# IMU.net
KiCad netlist of a schematic drawn in Altium Designer
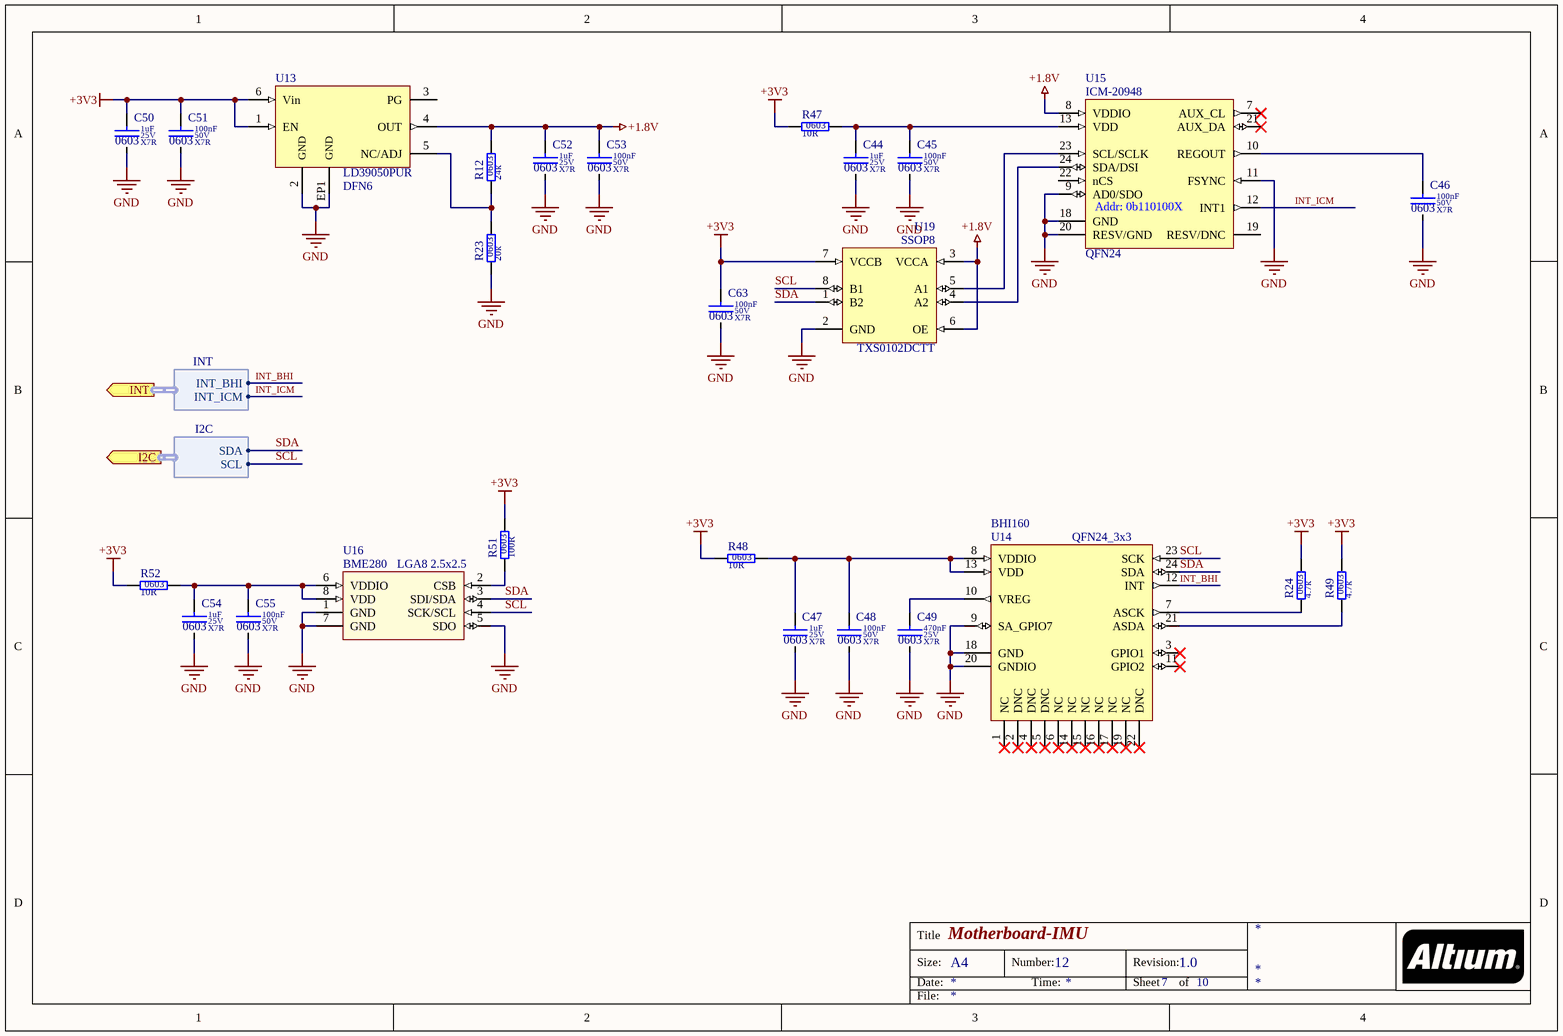
[diagram p0: IMU.SchDoc]

(export (version "E")
  (design (tool "Eeschema 10.0.6"))
  (components
    (comp (ref "C44")
      (value "1uF")
      (footprint "C_0603_1608")
      (description "Capacitor")
      (fields
        (field (name "DIELECTRIC") "X7R")
        (field (name "VOLTAGE") "25V")
        (field (name "SCH_FOOTPRINT") "0603")
        (field (name "PART NUMBER") "C_1uF_25V_X7R_0603_10")
        (field (name "MANUFACTURER") "Samsung")
      )
      (libsource (lib "Library") (part "C"))
    )
    (comp (ref "C45")
      (value "100nF")
      (footprint "C_0603_1608")
      (description "Capacitor")
      (fields
        (field (name "DIELECTRIC") "X7R")
        (field (name "VOLTAGE") "50V")
        (field (name "SCH_FOOTPRINT") "0603")
        (field (name "PART NUMBER") "C_100nF_50V_X7R_0603_5")
        (field (name "MANUFACTURER") "Samsung")
      )
      (libsource (lib "Library") (part "C"))
    )
    (comp (ref "C46")
      (value "100nF")
      (footprint "C_0603_1608")
      (description "Capacitor")
      (fields
        (field (name "DIELECTRIC") "X7R")
        (field (name "VOLTAGE") "50V")
        (field (name "SCH_FOOTPRINT") "0603")
        (field (name "PART NUMBER") "C_100nF_50V_X7R_0603_5")
        (field (name "MANUFACTURER") "Samsung")
      )
      (libsource (lib "Library") (part "C"))
    )
    (comp (ref "C47")
      (value "1uF")
      (footprint "C_0603_1608")
      (description "Capacitor")
      (fields
        (field (name "DIELECTRIC") "X7R")
        (field (name "VOLTAGE") "25V")
        (field (name "SCH_FOOTPRINT") "0603")
        (field (name "PART NUMBER") "C_1uF_25V_X7R_0603_10")
        (field (name "MANUFACTURER") "Samsung")
      )
      (libsource (lib "Library") (part "C"))
    )
    (comp (ref "C48")
      (value "100nF")
      (footprint "C_0603_1608")
      (description "Capacitor")
      (fields
        (field (name "DIELECTRIC") "X7R")
        (field (name "VOLTAGE") "50V")
        (field (name "SCH_FOOTPRINT") "0603")
        (field (name "PART NUMBER") "C_100nF_50V_X7R_0603_5")
        (field (name "MANUFACTURER") "Samsung")
      )
      (libsource (lib "Library") (part "C"))
    )
    (comp (ref "C49")
      (value "470nF")
      (footprint "C_0603_1608")
      (description "Capacitor")
      (fields
        (field (name "DIELECTRIC") "X7R")
        (field (name "VOLTAGE") "25V")
        (field (name "SCH_FOOTPRINT") "0603")
        (field (name "PART NUMBER") "C_470nF_25V_X7R_0603_10")
        (field (name "MANUFACTURER") "Murata")
      )
      (libsource (lib "Library") (part "C"))
    )
    (comp (ref "C50")
      (value "1uF")
      (footprint "C_0603_1608")
      (description "Capacitor")
      (fields
        (field (name "DIELECTRIC") "X7R")
        (field (name "VOLTAGE") "25V")
        (field (name "SCH_FOOTPRINT") "0603")
        (field (name "PART NUMBER") "C_1uF_25V_X7R_0603_10")
        (field (name "MANUFACTURER") "Samsung")
      )
      (libsource (lib "Library") (part "C"))
    )
    (comp (ref "C51")
      (value "100nF")
      (footprint "C_0603_1608")
      (description "Capacitor")
      (fields
        (field (name "DIELECTRIC") "X7R")
        (field (name "VOLTAGE") "50V")
        (field (name "SCH_FOOTPRINT") "0603")
        (field (name "PART NUMBER") "C_100nF_50V_X7R_0603_5")
        (field (name "MANUFACTURER") "Samsung")
      )
      (libsource (lib "Library") (part "C"))
    )
    (comp (ref "C52")
      (value "1uF")
      (footprint "C_0603_1608")
      (description "Capacitor")
      (fields
        (field (name "DIELECTRIC") "X7R")
        (field (name "VOLTAGE") "25V")
        (field (name "SCH_FOOTPRINT") "0603")
        (field (name "PART NUMBER") "C_1uF_25V_X7R_0603_10")
        (field (name "MANUFACTURER") "Samsung")
      )
      (libsource (lib "Library") (part "C"))
    )
    (comp (ref "C53")
      (value "100nF")
      (footprint "C_0603_1608")
      (description "Capacitor")
      (fields
        (field (name "DIELECTRIC") "X7R")
        (field (name "VOLTAGE") "50V")
        (field (name "SCH_FOOTPRINT") "0603")
        (field (name "PART NUMBER") "C_100nF_50V_X7R_0603_5")
        (field (name "MANUFACTURER") "Samsung")
      )
      (libsource (lib "Library") (part "C"))
    )
    (comp (ref "C54")
      (value "1uF")
      (footprint "C_0603_1608")
      (description "Capacitor")
      (fields
        (field (name "DIELECTRIC") "X7R")
        (field (name "VOLTAGE") "25V")
        (field (name "SCH_FOOTPRINT") "0603")
        (field (name "PART NUMBER") "C_1uF_25V_X7R_0603_10")
        (field (name "MANUFACTURER") "Samsung")
      )
      (libsource (lib "Library") (part "C"))
    )
    (comp (ref "C55")
      (value "100nF")
      (footprint "C_0603_1608")
      (description "Capacitor")
      (fields
        (field (name "DIELECTRIC") "X7R")
        (field (name "VOLTAGE") "50V")
        (field (name "SCH_FOOTPRINT") "0603")
        (field (name "PART NUMBER") "C_100nF_50V_X7R_0603_5")
        (field (name "MANUFACTURER") "Samsung")
      )
      (libsource (lib "Library") (part "C"))
    )
    (comp (ref "C63")
      (value "100nF")
      (footprint "C_0603_1608")
      (description "Capacitor")
      (fields
        (field (name "DIELECTRIC") "X7R")
        (field (name "VOLTAGE") "50V")
        (field (name "SCH_FOOTPRINT") "0603")
        (field (name "PART NUMBER") "C_100nF_50V_X7R_0603_5")
        (field (name "MANUFACTURER") "Samsung")
      )
      (libsource (lib "Library") (part "C"))
    )
    (comp (ref "R12")
      (value "24k")
      (footprint "R_0603_1608")
      (fields
        (field (name "SCH_FOOTPRINT") "0603")
        (field (name "PART NUMBER") "R_24k_0603_1")
        (field (name "VOLTAGE") "75V")
        (field (name "POWER") "100mW")
      )
      (libsource (lib "Library") (part "R"))
    )
    (comp (ref "R23")
      (value "20k")
      (footprint "R_0603_1608")
      (fields
        (field (name "SCH_FOOTPRINT") "0603")
        (field (name "PART NUMBER") "R_20k_0603_1")
        (field (name "VOLTAGE") "75V")
        (field (name "POWER") "100mW")
      )
      (libsource (lib "Library") (part "R"))
    )
    (comp (ref "R24")
      (value "4.7k")
      (footprint "R_0603_1608")
      (fields
        (field (name "SCH_FOOTPRINT") "0603")
        (field (name "PART NUMBER") "R_4.7k_0603_1")
        (field (name "VOLTAGE") "75V")
        (field (name "POWER") "100mW")
      )
      (libsource (lib "Library") (part "R"))
    )
    (comp (ref "R47")
      (value "10R")
      (footprint "R_0603_1608")
      (fields
        (field (name "SCH_FOOTPRINT") "0603")
        (field (name "PART NUMBER") "R_10R_0603_1")
        (field (name "VOLTAGE") "50V")
        (field (name "POWER") "100mW")
      )
      (libsource (lib "Library") (part "R"))
    )
    (comp (ref "R48")
      (value "10R")
      (footprint "R_0603_1608")
      (fields
        (field (name "SCH_FOOTPRINT") "0603")
        (field (name "PART NUMBER") "R_10R_0603_1")
        (field (name "VOLTAGE") "50V")
        (field (name "POWER") "100mW")
      )
      (libsource (lib "Library") (part "R"))
    )
    (comp (ref "R49")
      (value "4.7k")
      (footprint "R_0603_1608")
      (fields
        (field (name "SCH_FOOTPRINT") "0603")
        (field (name "PART NUMBER") "R_4.7k_0603_1")
        (field (name "VOLTAGE") "75V")
        (field (name "POWER") "100mW")
      )
      (libsource (lib "Library") (part "R"))
    )
    (comp (ref "R51")
      (value "100R")
      (footprint "R_0603_1608")
      (fields
        (field (name "SCH_FOOTPRINT") "0603")
        (field (name "PART NUMBER") "R_100R_0603_1")
        (field (name "VOLTAGE") "50V")
        (field (name "POWER") "100mW")
      )
      (libsource (lib "Library") (part "R"))
    )
    (comp (ref "R52")
      (value "10R")
      (footprint "R_0603_1608")
      (fields
        (field (name "SCH_FOOTPRINT") "0603")
        (field (name "PART NUMBER") "R_10R_0603_1")
        (field (name "VOLTAGE") "50V")
        (field (name "POWER") "100mW")
      )
      (libsource (lib "Library") (part "R"))
    )
    (comp (ref "U13")
      (value "LD39050PUR")
      (footprint "DFN6_3x3")
      (fields
        (field (name "SCH_FOOTPRINT") "DFN6")
        (field (name "PART NUMBER") "VL_LD39050PUR")
        (field (name "VOLTAGE") "ADJ")
        (field (name "MANUFACTURER") "STMicroelectronics")
      )
      (libsource (lib "Library") (part "VL_LD39050"))
    )
    (comp (ref "U14")
      (value "BHI160")
      (footprint "QFN24_3x3")
      (fields
        (field (name "SCH_FOOTPRINT") "QFN24_3x3")
        (field (name "PART NUMBER") "U_BHI160")
        (field (name "MANUFACTURER") "Bosch Tools")
        (field (name "Comment") "Three Axis Ultra Low Power Sensor Hub - LGA-24")
      )
      (libsource (lib "Library") (part "U_BHI160"))
    )
    (comp (ref "U15")
      (value "ICM-20948")
      (footprint "QFN24_3x3")
      (fields
        (field (name "SCH_FOOTPRINT") "QFN24")
        (field (name "PART NUMBER") "U_ICM-20948")
        (field (name "MANUFACTURER") "TDK")
        (field (name "Comment") "9-Axis MEMS MotionTracking Device")
      )
      (libsource (lib "Library") (part "U_ICM-20948"))
    )
    (comp (ref "U16")
      (value "BME280")
      (footprint "LGA8_2.5x2.5")
      (fields
        (field (name "SCH_FOOTPRINT") "LGA8 2.5x2.5")
        (field (name "PART NUMBER") "U_BME280")
        (field (name "MANUFACTURER") "Bosch Tools")
        (field (name "Comment") "Combined humidity and pressure sensor")
      )
      (libsource (lib "Library") (part "U_BME280"))
    )
    (comp (ref "U19")
      (value "TXS0102DCTT")
      (footprint "SSOP8_3x3")
      (fields
        (field (name "SCH_FOOTPRINT") "SSOP8")
        (field (name "PART NUMBER") "U_TXS0102DCTT")
        (field (name "MANUFACTURER") "Texas Instruments")
      )
      (libsource (lib "Library") (part "U_TXS0102_DCT_DCU"))
    )
  )
  (nets
    (net (code "3") (name "+1.8V") (class "Default")
      (node (ref "C52") (pin "1") (pinfunction "1_1") (pintype "passive"))
      (node (ref "C53") (pin "1") (pinfunction "1_1") (pintype "passive"))
      (node (ref "R12") (pin "2") (pinfunction "2_2") (pintype "passive"))
      (node (ref "U13") (pin "4") (pinfunction "OUT_4") (pintype "output"))
      (node (ref "U15") (pin "8") (pinfunction "VDDIO_8") (pintype "input"))
      (node (ref "U19") (pin "3") (pinfunction "VCCA_3") (pintype "input"))
      (node (ref "U19") (pin "6") (pinfunction "OE_6") (pintype "input"))
    )
    (net (code "4") (name "+3V3") (class "Default")
      (node (ref "C50") (pin "1") (pinfunction "1_1") (pintype "passive"))
      (node (ref "C51") (pin "1") (pinfunction "1_1") (pintype "passive"))
      (node (ref "C63") (pin "1") (pinfunction "1_1") (pintype "passive"))
      (node (ref "R24") (pin "2") (pinfunction "2_2") (pintype "passive"))
      (node (ref "R47") (pin "1") (pinfunction "1_1") (pintype "passive"))
      (node (ref "R48") (pin "1") (pinfunction "1_1") (pintype "passive"))
      (node (ref "R49") (pin "2") (pinfunction "2_2") (pintype "passive"))
      (node (ref "R51") (pin "2") (pinfunction "2_2") (pintype "passive"))
      (node (ref "R52") (pin "1") (pinfunction "1_1") (pintype "passive"))
      (node (ref "U13") (pin "1") (pinfunction "EN_1") (pintype "input"))
      (node (ref "U13") (pin "6") (pinfunction "Vin_6") (pintype "input"))
      (node (ref "U19") (pin "7") (pinfunction "VCCB_7") (pintype "input"))
    )
    (net (code "5") (name "/INT_BHI") (class "Default")
      (node (ref "U14") (pin "12") (pinfunction "INT_12") (pintype "output"))
    )
    (net (code "6") (name "/INT_ICM") (class "Default")
      (node (ref "U15") (pin "12") (pinfunction "INT1_12") (pintype "output"))
    )
    (net (code "7") (name "/SCL") (class "Default")
      (node (ref "U14") (pin "23") (pinfunction "SCK_23") (pintype "input"))
      (node (ref "U16") (pin "4") (pinfunction "SCK/SCL_4") (pintype "input"))
      (node (ref "U19") (pin "8") (pinfunction "B1_8") (pintype "bidirectional"))
    )
    (net (code "8") (name "/SDA") (class "Default")
      (node (ref "U14") (pin "24") (pinfunction "SDA_24") (pintype "bidirectional"))
      (node (ref "U16") (pin "3") (pinfunction "SDI/SDA_3") (pintype "bidirectional"))
      (node (ref "U19") (pin "1") (pinfunction "B2_1") (pintype "bidirectional"))
    )
    (net (code "11") (name "GND") (class "Default")
      (node (ref "C44") (pin "2") (pinfunction "2_2") (pintype "passive"))
      (node (ref "C45") (pin "2") (pinfunction "2_2") (pintype "passive"))
      (node (ref "C46") (pin "2") (pinfunction "2_2") (pintype "passive"))
      (node (ref "C47") (pin "2") (pinfunction "2_2") (pintype "passive"))
      (node (ref "C48") (pin "2") (pinfunction "2_2") (pintype "passive"))
      (node (ref "C49") (pin "2") (pinfunction "2_2") (pintype "passive"))
      (node (ref "C50") (pin "2") (pinfunction "2_2") (pintype "passive"))
      (node (ref "C51") (pin "2") (pinfunction "2_2") (pintype "passive"))
      (node (ref "C52") (pin "2") (pinfunction "2_2") (pintype "passive"))
      (node (ref "C53") (pin "2") (pinfunction "2_2") (pintype "passive"))
      (node (ref "C54") (pin "2") (pinfunction "2_2") (pintype "passive"))
      (node (ref "C55") (pin "2") (pinfunction "2_2") (pintype "passive"))
      (node (ref "C63") (pin "2") (pinfunction "2_2") (pintype "passive"))
      (node (ref "R23") (pin "1") (pinfunction "1_1") (pintype "passive"))
      (node (ref "U13") (pin "2") (pinfunction "GND_2") (pintype "power_in"))
      (node (ref "U13") (pin "EP1") (pinfunction "GND_EP1") (pintype "power_in"))
      (node (ref "U14") (pin "18") (pinfunction "GND_18") (pintype "power_in"))
      (node (ref "U14") (pin "20") (pinfunction "GNDIO_20") (pintype "power_in"))
      (node (ref "U14") (pin "9") (pinfunction "SA_GPIO7_9") (pintype "bidirectional"))
      (node (ref "U15") (pin "11") (pinfunction "FSYNC_11") (pintype "input"))
      (node (ref "U15") (pin "18") (pinfunction "GND_18") (pintype "power_in"))
      (node (ref "U15") (pin "20") (pinfunction "RESV/GND_20") (pintype "power_in"))
      (node (ref "U15") (pin "9") (pinfunction "AD0/SDO_9") (pintype "bidirectional"))
      (node (ref "U16") (pin "1") (pinfunction "GND_1") (pintype "power_in"))
      (node (ref "U16") (pin "5") (pinfunction "SDO_5") (pintype "bidirectional"))
      (node (ref "U16") (pin "7") (pinfunction "GND_7") (pintype "power_in"))
      (node (ref "U19") (pin "2") (pinfunction "GND_2") (pintype "power_in"))
    )
    (net (code "12") (name "Net-(U13-NC{slash}ADJ)") (class "Default")
      (node (ref "R12") (pin "1") (pinfunction "1_1") (pintype "passive"))
      (node (ref "R23") (pin "2") (pinfunction "2_2") (pintype "passive"))
      (node (ref "U13") (pin "5") (pinfunction "NC/ADJ_5") (pintype "passive"))
    )
    (net (code "13") (name "Net-(U14-ASCK)") (class "Default")
      (node (ref "R24") (pin "1") (pinfunction "1_1") (pintype "passive"))
      (node (ref "U14") (pin "7") (pinfunction "ASCK_7") (pintype "output"))
    )
    (net (code "14") (name "Net-(U14-ASDA)") (class "Default")
      (node (ref "R49") (pin "1") (pinfunction "1_1") (pintype "passive"))
      (node (ref "U14") (pin "21") (pinfunction "ASDA_21") (pintype "bidirectional"))
    )
    (net (code "15") (name "Net-(U14-VDD)") (class "Default")
      (node (ref "C47") (pin "1") (pinfunction "1_1") (pintype "passive"))
      (node (ref "C48") (pin "1") (pinfunction "1_1") (pintype "passive"))
      (node (ref "R48") (pin "2") (pinfunction "2_2") (pintype "passive"))
      (node (ref "U14") (pin "13") (pinfunction "VDD_13") (pintype "input"))
      (node (ref "U14") (pin "8") (pinfunction "VDDIO_8") (pintype "input"))
    )
    (net (code "16") (name "Net-(U14-VREG)") (class "Default")
      (node (ref "C49") (pin "1") (pinfunction "1_1") (pintype "passive"))
      (node (ref "U14") (pin "10") (pinfunction "VREG_10") (pintype "output"))
    )
    (net (code "17") (name "Net-(U15-REGOUT)") (class "Default")
      (node (ref "C46") (pin "1") (pinfunction "1_1") (pintype "passive"))
      (node (ref "U15") (pin "10") (pinfunction "REGOUT_10") (pintype "output"))
    )
    (net (code "18") (name "Net-(U15-SCL{slash}SCLK)") (class "Default")
      (node (ref "U15") (pin "23") (pinfunction "SCL/SCLK_23") (pintype "input"))
      (node (ref "U19") (pin "5") (pinfunction "A1_5") (pintype "bidirectional"))
    )
    (net (code "19") (name "Net-(U15-SDA{slash}DSI)") (class "Default")
      (node (ref "U15") (pin "24") (pinfunction "SDA/DSI_24") (pintype "bidirectional"))
      (node (ref "U19") (pin "4") (pinfunction "A2_4") (pintype "bidirectional"))
    )
    (net (code "20") (name "Net-(U15-VDD)") (class "Default")
      (node (ref "C44") (pin "1") (pinfunction "1_1") (pintype "passive"))
      (node (ref "C45") (pin "1") (pinfunction "1_1") (pintype "passive"))
      (node (ref "R47") (pin "2") (pinfunction "2_2") (pintype "passive"))
      (node (ref "U15") (pin "13") (pinfunction "VDD_13") (pintype "input"))
    )
    (net (code "21") (name "Net-(U16-CSB)") (class "Default")
      (node (ref "R51") (pin "1") (pinfunction "1_1") (pintype "passive"))
      (node (ref "U16") (pin "2") (pinfunction "CSB_2") (pintype "input"))
    )
    (net (code "22") (name "Net-(U16-VDD)") (class "Default")
      (node (ref "C54") (pin "1") (pinfunction "1_1") (pintype "passive"))
      (node (ref "C55") (pin "1") (pinfunction "1_1") (pintype "passive"))
      (node (ref "R52") (pin "2") (pinfunction "2_2") (pintype "passive"))
      (node (ref "U16") (pin "6") (pinfunction "VDDIO_6") (pintype "input"))
      (node (ref "U16") (pin "8") (pinfunction "VDD_8") (pintype "input"))
    )
    (net (code "23") (name "unconnected-(U13-PG-Pad3)") (class "Default")
      (node (ref "U13") (pin "3") (pinfunction "PG_3") (pintype "passive"))
    )
    (net (code "24") (name "unconnected-(U14-DNC-Pad2)") (class "Default")
      (node (ref "U14") (pin "2") (pinfunction "DNC_2") (pintype "passive+no_connect"))
    )
    (net (code "25") (name "unconnected-(U14-DNC-Pad4)") (class "Default")
      (node (ref "U14") (pin "4") (pinfunction "DNC_4") (pintype "passive+no_connect"))
    )
    (net (code "26") (name "unconnected-(U14-DNC-Pad5)") (class "Default")
      (node (ref "U14") (pin "5") (pinfunction "DNC_5") (pintype "passive+no_connect"))
    )
    (net (code "27") (name "unconnected-(U14-DNC-Pad22)") (class "Default")
      (node (ref "U14") (pin "22") (pinfunction "DNC_22") (pintype "passive+no_connect"))
    )
    (net (code "28") (name "unconnected-(U14-GPIO1-Pad3)") (class "Default")
      (node (ref "U14") (pin "3") (pinfunction "GPIO1_3") (pintype "bidirectional+no_connect"))
    )
    (net (code "29") (name "unconnected-(U14-GPIO2-Pad11)") (class "Default")
      (node (ref "U14") (pin "11") (pinfunction "GPIO2_11") (pintype "bidirectional+no_connect"))
    )
    (net (code "30") (name "unconnected-(U14-NC-Pad1)") (class "Default")
      (node (ref "U14") (pin "1") (pinfunction "NC_1") (pintype "passive+no_connect"))
    )
    (net (code "31") (name "unconnected-(U14-NC-Pad6)") (class "Default")
      (node (ref "U14") (pin "6") (pinfunction "NC_6") (pintype "passive+no_connect"))
    )
    (net (code "32") (name "unconnected-(U14-NC-Pad14)") (class "Default")
      (node (ref "U14") (pin "14") (pinfunction "NC_14") (pintype "passive+no_connect"))
    )
    (net (code "33") (name "unconnected-(U14-NC-Pad15)") (class "Default")
      (node (ref "U14") (pin "15") (pinfunction "NC_15") (pintype "passive+no_connect"))
    )
    (net (code "34") (name "unconnected-(U14-NC-Pad16)") (class "Default")
      (node (ref "U14") (pin "16") (pinfunction "NC_16") (pintype "passive+no_connect"))
    )
    (net (code "35") (name "unconnected-(U14-NC-Pad17)") (class "Default")
      (node (ref "U14") (pin "17") (pinfunction "NC_17") (pintype "passive+no_connect"))
    )
    (net (code "36") (name "unconnected-(U14-NC-Pad19)") (class "Default")
      (node (ref "U14") (pin "19") (pinfunction "NC_19") (pintype "passive+no_connect"))
    )
    (net (code "37") (name "unconnected-(U15-AUX_CL-Pad7)") (class "Default")
      (node (ref "U15") (pin "7") (pinfunction "AUX_CL_7") (pintype "output+no_connect"))
    )
    (net (code "38") (name "unconnected-(U15-AUX_DA-Pad21)") (class "Default")
      (node (ref "U15") (pin "21") (pinfunction "AUX_DA_21") (pintype "bidirectional+no_connect"))
    )
    (net (code "39") (name "unconnected-(U15-DNC-Pad1)") (class "Default")
      (node (ref "U15") (pin "1") (pinfunction "DNC_1") (pintype "passive"))
    )
    (net (code "40") (name "unconnected-(U15-DNC-Pad2)") (class "Default")
      (node (ref "U15") (pin "2") (pinfunction "DNC_2") (pintype "passive"))
    )
    (net (code "41") (name "unconnected-(U15-DNC-Pad3)") (class "Default")
      (node (ref "U15") (pin "3") (pinfunction "DNC_3") (pintype "passive"))
    )
    (net (code "42") (name "unconnected-(U15-DNC-Pad4)") (class "Default")
      (node (ref "U15") (pin "4") (pinfunction "DNC_4") (pintype "passive"))
    )
    (net (code "43") (name "unconnected-(U15-DNC-Pad5)") (class "Default")
      (node (ref "U15") (pin "5") (pinfunction "DNC_5") (pintype "passive"))
    )
    (net (code "44") (name "unconnected-(U15-DNC-Pad6)") (class "Default")
      (node (ref "U15") (pin "6") (pinfunction "DNC_6") (pintype "passive"))
    )
    (net (code "45") (name "unconnected-(U15-DNC-Pad14)") (class "Default")
      (node (ref "U15") (pin "14") (pinfunction "DNC_14") (pintype "passive"))
    )
    (net (code "46") (name "unconnected-(U15-DNC-Pad15)") (class "Default")
      (node (ref "U15") (pin "15") (pinfunction "DNC_15") (pintype "passive"))
    )
    (net (code "47") (name "unconnected-(U15-DNC-Pad16)") (class "Default")
      (node (ref "U15") (pin "16") (pinfunction "DNC_16") (pintype "passive"))
    )
    (net (code "48") (name "unconnected-(U15-DNC-Pad17)") (class "Default")
      (node (ref "U15") (pin "17") (pinfunction "DNC_17") (pintype "passive"))
    )
    (net (code "49") (name "unconnected-(U15-RESV{slash}DNC-Pad19)") (class "Default")
      (node (ref "U15") (pin "19") (pinfunction "RESV/DNC_19") (pintype "passive"))
    )
    (net (code "50") (name "unconnected-(U15-nCS-Pad22)") (class "Default")
      (node (ref "U15") (pin "22") (pinfunction "nCS_22") (pintype "input"))
    )
  )
)
